# Push_Pull_Pot_Breakout.net
KiCad netlist of a schematic drawn in Altium Designer
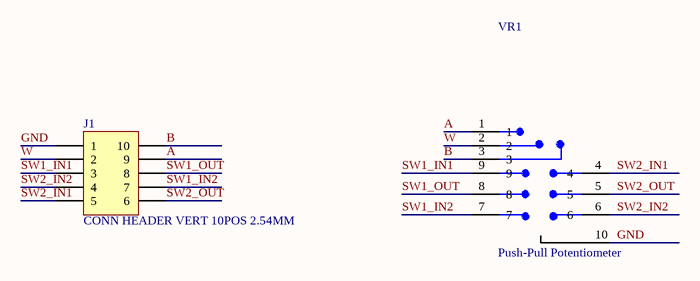
[diagram p0: Push_Pull_Pot_Breakout.SchDoc]

(export (version "E")
  (design (tool "Eeschema 10.0.6"))
  (components
    (comp (ref "J1")
      (value "CONN HEADER VERT 10POS 2.54MM")
      (footprint "CONN HEADER VERT 10POS 2.54MM")
      (description "Connector Header Through Hole 10 position 0.100\" (2.54mm)")
      (fields (field (name "MANUFACTURER") "Samtec Inc.") (field (name "DIGIKEY PART NUMBER") "SAM8999-ND"))
      (libsource (lib "GuitarLibrary") (part "CONN HEADER VERT 10POS 2.54MM"))
    )
    (comp (ref "VR1")
      (value "Push-Pull Potentiometer")
      (footprint "PUSH-PULL POTENTIOMETER")
      (libsource (lib "GuitarLibrary") (part "Push-Pull Potentiometer"))
    )
  )
  (nets
    (net (code "1") (name "/A") (class "Default")
      (node (ref "J1") (pin "9") (pinfunction "9_9") (pintype "passive"))
      (node (ref "VR1") (pin "1") (pinfunction "1_1") (pintype "passive"))
    )
    (net (code "2") (name "/B") (class "Default")
      (node (ref "J1") (pin "10") (pinfunction "10_10") (pintype "passive"))
      (node (ref "VR1") (pin "3") (pinfunction "3_3") (pintype "passive"))
    )
    (net (code "3") (name "/GND") (class "Default")
      (node (ref "J1") (pin "1") (pinfunction "1_1") (pintype "passive"))
      (node (ref "VR1") (pin "10") (pinfunction "10_10") (pintype "passive"))
    )
    (net (code "4") (name "/SW1_IN1") (class "Default")
      (node (ref "J1") (pin "3") (pinfunction "3_3") (pintype "passive"))
      (node (ref "VR1") (pin "9") (pinfunction "9_9") (pintype "passive"))
    )
    (net (code "5") (name "/SW1_IN2") (class "Default")
      (node (ref "J1") (pin "7") (pinfunction "7_7") (pintype "passive"))
      (node (ref "VR1") (pin "7") (pinfunction "7_7") (pintype "passive"))
    )
    (net (code "6") (name "/SW1_OUT") (class "Default")
      (node (ref "J1") (pin "8") (pinfunction "8_8") (pintype "passive"))
      (node (ref "VR1") (pin "8") (pinfunction "8_8") (pintype "passive"))
    )
    (net (code "7") (name "/SW2_IN1") (class "Default")
      (node (ref "J1") (pin "5") (pinfunction "5_5") (pintype "passive"))
      (node (ref "VR1") (pin "4") (pinfunction "4_4") (pintype "passive"))
    )
    (net (code "8") (name "/SW2_IN2") (class "Default")
      (node (ref "J1") (pin "4") (pinfunction "4_4") (pintype "passive"))
      (node (ref "VR1") (pin "6") (pinfunction "6_6") (pintype "passive"))
    )
    (net (code "9") (name "/SW2_OUT") (class "Default")
      (node (ref "J1") (pin "6") (pinfunction "6_6") (pintype "passive"))
      (node (ref "VR1") (pin "5") (pinfunction "5_5") (pintype "passive"))
    )
    (net (code "10") (name "/W") (class "Default")
      (node (ref "J1") (pin "2") (pinfunction "2_2") (pintype "passive"))
      (node (ref "VR1") (pin "2") (pinfunction "2_2") (pintype "passive"))
    )
  )
)
